# bancada_hx711_5.net
KiCad netlist of a schematic drawn in EAGLE
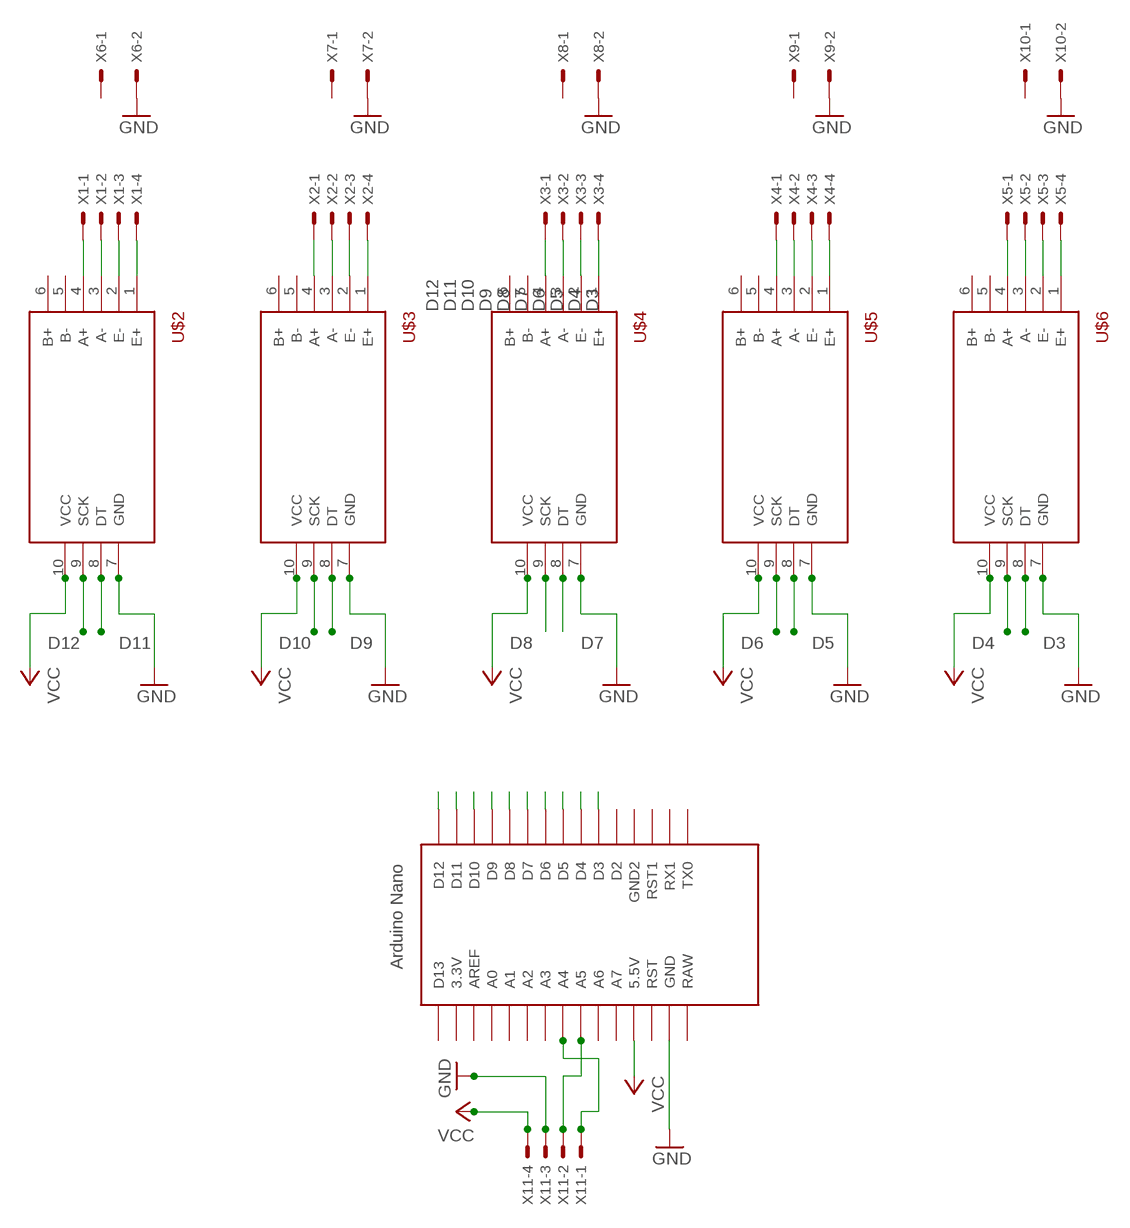
[diagram p0: schematic, sheet 1]

(export (version "E")
  (design (tool "Eeschema 10.0.6"))
  (components
    (comp (ref "U$1")
      (value "NANO")
      (footprint "eagle-import:NANO")
      (libsource (lib "eagle-import") (part "NANO"))
    )
    (comp (ref "U$2")
      (value "HX711-1")
      (footprint "eagle-import:HX711-1")
      (libsource (lib "eagle-import") (part "HX711-1"))
    )
    (comp (ref "U$3")
      (value "HX711-1")
      (footprint "eagle-import:HX711-1")
      (libsource (lib "eagle-import") (part "HX711-1"))
    )
    (comp (ref "U$4")
      (value "HX711-1")
      (footprint "eagle-import:HX711-1")
      (libsource (lib "eagle-import") (part "HX711-1"))
    )
    (comp (ref "U$5")
      (value "HX711-1")
      (footprint "eagle-import:HX711-1")
      (libsource (lib "eagle-import") (part "HX711-1"))
    )
    (comp (ref "U$6")
      (value "HX711-1")
      (footprint "eagle-import:HX711-1")
      (libsource (lib "eagle-import") (part "HX711-1"))
    )
    (comp (ref "X1")
      (value "KK-156-4")
      (footprint "eagle-import:KK-156-4")
      (fields (field (name "MF") "MOLEX"))
      (libsource (lib "eagle-import") (part "KK-156-4"))
    )
    (comp (ref "X2")
      (value "KK-156-4")
      (footprint "eagle-import:KK-156-4")
      (fields (field (name "MF") "MOLEX"))
      (libsource (lib "eagle-import") (part "KK-156-4"))
    )
    (comp (ref "X3")
      (value "KK-156-4")
      (footprint "eagle-import:KK-156-4")
      (fields (field (name "MF") "MOLEX"))
      (libsource (lib "eagle-import") (part "KK-156-4"))
    )
    (comp (ref "X4")
      (value "KK-156-4")
      (footprint "eagle-import:KK-156-4")
      (fields (field (name "MF") "MOLEX"))
      (libsource (lib "eagle-import") (part "KK-156-4"))
    )
    (comp (ref "X5")
      (value "KK-156-4")
      (footprint "eagle-import:KK-156-4")
      (fields (field (name "MF") "MOLEX"))
      (libsource (lib "eagle-import") (part "KK-156-4"))
    )
    (comp (ref "X6")
      (value "KK-156-2")
      (footprint "eagle-import:KK-156-2")
      (fields (field (name "MF") "MOLEX"))
      (libsource (lib "eagle-import") (part "KK-156-2"))
    )
    (comp (ref "X7")
      (value "KK-156-2")
      (footprint "eagle-import:KK-156-2")
      (fields (field (name "MF") "MOLEX"))
      (libsource (lib "eagle-import") (part "KK-156-2"))
    )
    (comp (ref "X8")
      (value "KK-156-2")
      (footprint "eagle-import:KK-156-2")
      (fields (field (name "MF") "MOLEX"))
      (libsource (lib "eagle-import") (part "KK-156-2"))
    )
    (comp (ref "X9")
      (value "KK-156-2")
      (footprint "eagle-import:KK-156-2")
      (fields (field (name "MF") "MOLEX"))
      (libsource (lib "eagle-import") (part "KK-156-2"))
    )
    (comp (ref "X10")
      (value "KK-156-2")
      (footprint "eagle-import:KK-156-2")
      (fields (field (name "MF") "MOLEX"))
      (libsource (lib "eagle-import") (part "KK-156-2"))
    )
    (comp (ref "X11")
      (value "KK-156-4")
      (footprint "eagle-import:KK-156-4")
      (fields (field (name "MF") "MOLEX"))
      (libsource (lib "eagle-import") (part "KK-156-4"))
    )
  )
  (nets
    (net (code "1") (name "/D3") (class "Default")
      (node (ref "U$1") (pin "D3") (pinfunction "D3_D3") (pintype "bidirectional"))
      (node (ref "U$6") (pin "8") (pinfunction "DT_8") (pintype "bidirectional"))
    )
    (net (code "2") (name "/D4") (class "Default")
      (node (ref "U$1") (pin "D4") (pinfunction "D4_D4") (pintype "bidirectional"))
      (node (ref "U$6") (pin "9") (pinfunction "SCK_9") (pintype "bidirectional"))
    )
    (net (code "3") (name "/D5") (class "Default")
      (node (ref "U$1") (pin "D5") (pinfunction "D5_D5") (pintype "bidirectional"))
      (node (ref "U$5") (pin "8") (pinfunction "DT_8") (pintype "bidirectional"))
    )
    (net (code "4") (name "/D6") (class "Default")
      (node (ref "U$1") (pin "D6") (pinfunction "D6_D6") (pintype "bidirectional"))
      (node (ref "U$5") (pin "9") (pinfunction "SCK_9") (pintype "bidirectional"))
    )
    (net (code "5") (name "/D7") (class "Default")
      (node (ref "U$1") (pin "D7") (pinfunction "D7_D7") (pintype "bidirectional"))
      (node (ref "U$4") (pin "8") (pinfunction "DT_8") (pintype "bidirectional"))
    )
    (net (code "6") (name "/D8") (class "Default")
      (node (ref "U$1") (pin "D8") (pinfunction "D8_D8") (pintype "bidirectional"))
      (node (ref "U$4") (pin "9") (pinfunction "SCK_9") (pintype "bidirectional"))
    )
    (net (code "7") (name "/D9") (class "Default")
      (node (ref "U$1") (pin "D9") (pinfunction "D9_D9") (pintype "bidirectional"))
      (node (ref "U$3") (pin "8") (pinfunction "DT_8") (pintype "bidirectional"))
    )
    (net (code "8") (name "/D10") (class "Default")
      (node (ref "U$1") (pin "D10") (pinfunction "D10_D10") (pintype "bidirectional"))
      (node (ref "U$3") (pin "9") (pinfunction "SCK_9") (pintype "bidirectional"))
    )
    (net (code "9") (name "/D11") (class "Default")
      (node (ref "U$1") (pin "D11") (pinfunction "D11_D11") (pintype "bidirectional"))
      (node (ref "U$2") (pin "8") (pinfunction "DT_8") (pintype "bidirectional"))
    )
    (net (code "10") (name "/D12") (class "Default")
      (node (ref "U$1") (pin "D12") (pinfunction "D12_D12") (pintype "bidirectional"))
      (node (ref "U$2") (pin "9") (pinfunction "SCK_9") (pintype "bidirectional"))
    )
    (net (code "11") (name "GND") (class "Default")
      (node (ref "U$1") (pin "GND") (pinfunction "GND_GND") (pintype "bidirectional"))
      (node (ref "U$2") (pin "7") (pinfunction "GND_7") (pintype "bidirectional"))
      (node (ref "U$3") (pin "7") (pinfunction "GND_7") (pintype "bidirectional"))
      (node (ref "U$4") (pin "7") (pinfunction "GND_7") (pintype "bidirectional"))
      (node (ref "U$5") (pin "7") (pinfunction "GND_7") (pintype "bidirectional"))
      (node (ref "U$6") (pin "7") (pinfunction "GND_7") (pintype "bidirectional"))
      (node (ref "X10") (pin "2") (pinfunction "S_2") (pintype "passive"))
      (node (ref "X11") (pin "3") (pinfunction "S_3") (pintype "passive"))
      (node (ref "X6") (pin "2") (pinfunction "S_2") (pintype "passive"))
      (node (ref "X7") (pin "2") (pinfunction "S_2") (pintype "passive"))
      (node (ref "X8") (pin "2") (pinfunction "S_2") (pintype "passive"))
      (node (ref "X9") (pin "2") (pinfunction "S_2") (pintype "passive"))
    )
    (net (code "12") (name "Net-(U$2-A+)") (class "Default")
      (node (ref "U$2") (pin "4") (pinfunction "A+_4") (pintype "bidirectional"))
      (node (ref "X1") (pin "1") (pinfunction "S_1") (pintype "passive"))
    )
    (net (code "13") (name "Net-(U$2-A-)") (class "Default")
      (node (ref "U$2") (pin "3") (pinfunction "A-_3") (pintype "bidirectional"))
      (node (ref "X1") (pin "2") (pinfunction "S_2") (pintype "passive"))
    )
    (net (code "14") (name "Net-(U$2-E+)") (class "Default")
      (node (ref "U$2") (pin "1") (pinfunction "E+_1") (pintype "bidirectional"))
      (node (ref "X1") (pin "4") (pinfunction "S_4") (pintype "passive"))
    )
    (net (code "15") (name "Net-(U$2-E-)") (class "Default")
      (node (ref "U$2") (pin "2") (pinfunction "E-_2") (pintype "bidirectional"))
      (node (ref "X1") (pin "3") (pinfunction "S_3") (pintype "passive"))
    )
    (net (code "16") (name "Net-(U$3-A+)") (class "Default")
      (node (ref "U$3") (pin "4") (pinfunction "A+_4") (pintype "bidirectional"))
      (node (ref "X2") (pin "1") (pinfunction "S_1") (pintype "passive"))
    )
    (net (code "17") (name "Net-(U$3-A-)") (class "Default")
      (node (ref "U$3") (pin "3") (pinfunction "A-_3") (pintype "bidirectional"))
      (node (ref "X2") (pin "2") (pinfunction "S_2") (pintype "passive"))
    )
    (net (code "18") (name "Net-(U$3-E+)") (class "Default")
      (node (ref "U$3") (pin "1") (pinfunction "E+_1") (pintype "bidirectional"))
      (node (ref "X2") (pin "4") (pinfunction "S_4") (pintype "passive"))
    )
    (net (code "19") (name "Net-(U$3-E-)") (class "Default")
      (node (ref "U$3") (pin "2") (pinfunction "E-_2") (pintype "bidirectional"))
      (node (ref "X2") (pin "3") (pinfunction "S_3") (pintype "passive"))
    )
    (net (code "20") (name "Net-(U$4-A+)") (class "Default")
      (node (ref "U$4") (pin "4") (pinfunction "A+_4") (pintype "bidirectional"))
      (node (ref "X3") (pin "1") (pinfunction "S_1") (pintype "passive"))
    )
    (net (code "21") (name "Net-(U$4-A-)") (class "Default")
      (node (ref "U$4") (pin "3") (pinfunction "A-_3") (pintype "bidirectional"))
      (node (ref "X3") (pin "2") (pinfunction "S_2") (pintype "passive"))
    )
    (net (code "22") (name "Net-(U$4-E+)") (class "Default")
      (node (ref "U$4") (pin "1") (pinfunction "E+_1") (pintype "bidirectional"))
      (node (ref "X3") (pin "4") (pinfunction "S_4") (pintype "passive"))
    )
    (net (code "23") (name "Net-(U$4-E-)") (class "Default")
      (node (ref "U$4") (pin "2") (pinfunction "E-_2") (pintype "bidirectional"))
      (node (ref "X3") (pin "3") (pinfunction "S_3") (pintype "passive"))
    )
    (net (code "24") (name "Net-(U$5-A+)") (class "Default")
      (node (ref "U$5") (pin "4") (pinfunction "A+_4") (pintype "bidirectional"))
      (node (ref "X4") (pin "1") (pinfunction "S_1") (pintype "passive"))
    )
    (net (code "25") (name "Net-(U$5-A-)") (class "Default")
      (node (ref "U$5") (pin "3") (pinfunction "A-_3") (pintype "bidirectional"))
      (node (ref "X4") (pin "2") (pinfunction "S_2") (pintype "passive"))
    )
    (net (code "26") (name "Net-(U$5-E+)") (class "Default")
      (node (ref "U$5") (pin "1") (pinfunction "E+_1") (pintype "bidirectional"))
      (node (ref "X4") (pin "4") (pinfunction "S_4") (pintype "passive"))
    )
    (net (code "27") (name "Net-(U$5-E-)") (class "Default")
      (node (ref "U$5") (pin "2") (pinfunction "E-_2") (pintype "bidirectional"))
      (node (ref "X4") (pin "3") (pinfunction "S_3") (pintype "passive"))
    )
    (net (code "28") (name "Net-(U$6-A+)") (class "Default")
      (node (ref "U$6") (pin "4") (pinfunction "A+_4") (pintype "bidirectional"))
      (node (ref "X5") (pin "1") (pinfunction "S_1") (pintype "passive"))
    )
    (net (code "29") (name "Net-(U$6-A-)") (class "Default")
      (node (ref "U$6") (pin "3") (pinfunction "A-_3") (pintype "bidirectional"))
      (node (ref "X5") (pin "2") (pinfunction "S_2") (pintype "passive"))
    )
    (net (code "30") (name "Net-(U$6-E+)") (class "Default")
      (node (ref "U$6") (pin "1") (pinfunction "E+_1") (pintype "bidirectional"))
      (node (ref "X5") (pin "4") (pinfunction "S_4") (pintype "passive"))
    )
    (net (code "31") (name "Net-(U$6-E-)") (class "Default")
      (node (ref "U$6") (pin "2") (pinfunction "E-_2") (pintype "bidirectional"))
      (node (ref "X5") (pin "3") (pinfunction "S_3") (pintype "passive"))
    )
    (net (code "32") (name "Net-(X11A-S)") (class "Default")
      (node (ref "U$1") (pin "A4") (pinfunction "A4_A4") (pintype "bidirectional"))
      (node (ref "X11") (pin "1") (pinfunction "S_1") (pintype "passive"))
    )
    (net (code "33") (name "Net-(X11B-S)") (class "Default")
      (node (ref "U$1") (pin "A5") (pinfunction "A5_A5") (pintype "bidirectional"))
      (node (ref "X11") (pin "2") (pinfunction "S_2") (pintype "passive"))
    )
    (net (code "34") (name "VCC") (class "Default")
      (node (ref "U$1") (pin "5V") (pinfunction "5.5V_5V") (pintype "bidirectional"))
      (node (ref "U$2") (pin "10") (pinfunction "VCC_10") (pintype "bidirectional"))
      (node (ref "U$3") (pin "10") (pinfunction "VCC_10") (pintype "bidirectional"))
      (node (ref "U$4") (pin "10") (pinfunction "VCC_10") (pintype "bidirectional"))
      (node (ref "U$5") (pin "10") (pinfunction "VCC_10") (pintype "bidirectional"))
      (node (ref "U$6") (pin "10") (pinfunction "VCC_10") (pintype "bidirectional"))
      (node (ref "X11") (pin "4") (pinfunction "S_4") (pintype "passive"))
    )
    (net (code "35") (name "unconnected-(U$1-GND2-PadGND1)") (class "Default")
      (node (ref "U$1") (pin "GND1") (pinfunction "GND2_GND1") (pintype "bidirectional"))
    )
    (net (code "36") (name "unconnected-(U$1-Pad3.3V)") (class "Default")
      (node (ref "U$1") (pin "3.3V") (pinfunction "3.3V_3.3V") (pintype "bidirectional"))
    )
    (net (code "37") (name "unconnected-(U$1-PadA0)") (class "Default")
      (node (ref "U$1") (pin "A0") (pinfunction "A0_A0") (pintype "bidirectional"))
    )
    (net (code "38") (name "unconnected-(U$1-PadA1)") (class "Default")
      (node (ref "U$1") (pin "A1") (pinfunction "A1_A1") (pintype "bidirectional"))
    )
    (net (code "39") (name "unconnected-(U$1-PadA2)") (class "Default")
      (node (ref "U$1") (pin "A2") (pinfunction "A2_A2") (pintype "bidirectional"))
    )
    (net (code "40") (name "unconnected-(U$1-PadA3)") (class "Default")
      (node (ref "U$1") (pin "A3") (pinfunction "A3_A3") (pintype "bidirectional"))
    )
    (net (code "41") (name "unconnected-(U$1-PadA6)") (class "Default")
      (node (ref "U$1") (pin "A6") (pinfunction "A6_A6") (pintype "bidirectional"))
    )
    (net (code "42") (name "unconnected-(U$1-PadA7)") (class "Default")
      (node (ref "U$1") (pin "A7") (pinfunction "A7_A7") (pintype "bidirectional"))
    )
    (net (code "43") (name "unconnected-(U$1-PadAREF)") (class "Default")
      (node (ref "U$1") (pin "AREF") (pinfunction "AREF_AREF") (pintype "bidirectional"))
    )
    (net (code "44") (name "unconnected-(U$1-PadD2)") (class "Default")
      (node (ref "U$1") (pin "D2") (pinfunction "D2_D2") (pintype "bidirectional"))
    )
    (net (code "45") (name "unconnected-(U$1-PadD13)") (class "Default")
      (node (ref "U$1") (pin "D13") (pinfunction "D13_D13") (pintype "bidirectional"))
    )
    (net (code "46") (name "unconnected-(U$1-PadICSP1)") (class "Default")
      (node (ref "U$1") (pin "ICSP1") (pinfunction "ICSP1_ICSP1") (pintype "bidirectional"))
    )
    (net (code "47") (name "unconnected-(U$1-PadICSP2)") (class "Default")
      (node (ref "U$1") (pin "ICSP2") (pinfunction "ICSP2_ICSP2") (pintype "bidirectional"))
    )
    (net (code "48") (name "unconnected-(U$1-PadICSP3)") (class "Default")
      (node (ref "U$1") (pin "ICSP3") (pinfunction "ICSP3_ICSP3") (pintype "bidirectional"))
    )
    (net (code "49") (name "unconnected-(U$1-PadICSP4)") (class "Default")
      (node (ref "U$1") (pin "ICSP4") (pinfunction "ICSP4_ICSP4") (pintype "bidirectional"))
    )
    (net (code "50") (name "unconnected-(U$1-PadICSP5)") (class "Default")
      (node (ref "U$1") (pin "ICSP5") (pinfunction "ICSP5_ICSP5") (pintype "bidirectional"))
    )
    (net (code "51") (name "unconnected-(U$1-PadICSP6)") (class "Default")
      (node (ref "U$1") (pin "ICSP6") (pinfunction "ICSP6_ICSP6") (pintype "bidirectional"))
    )
    (net (code "52") (name "unconnected-(U$1-PadRAW)") (class "Default")
      (node (ref "U$1") (pin "RAW") (pinfunction "RAW_RAW") (pintype "bidirectional"))
    )
    (net (code "53") (name "unconnected-(U$1-PadRST)") (class "Default")
      (node (ref "U$1") (pin "RST") (pinfunction "RST_RST") (pintype "bidirectional"))
    )
    (net (code "54") (name "unconnected-(U$1-PadRST1)") (class "Default")
      (node (ref "U$1") (pin "RST1") (pinfunction "RST1_RST1") (pintype "bidirectional"))
    )
    (net (code "55") (name "unconnected-(U$1-PadRX1)") (class "Default")
      (node (ref "U$1") (pin "RX1") (pinfunction "RX1_RX1") (pintype "bidirectional"))
    )
    (net (code "56") (name "unconnected-(U$1-PadTX0)") (class "Default")
      (node (ref "U$1") (pin "TX0") (pinfunction "TX0_TX0") (pintype "bidirectional"))
    )
    (net (code "57") (name "unconnected-(U$2-B+-Pad6)") (class "Default")
      (node (ref "U$2") (pin "6") (pinfunction "B+_6") (pintype "bidirectional"))
    )
    (net (code "58") (name "unconnected-(U$2-B--Pad5)") (class "Default")
      (node (ref "U$2") (pin "5") (pinfunction "B-_5") (pintype "bidirectional"))
    )
    (net (code "59") (name "unconnected-(U$3-B+-Pad6)") (class "Default")
      (node (ref "U$3") (pin "6") (pinfunction "B+_6") (pintype "bidirectional"))
    )
    (net (code "60") (name "unconnected-(U$3-B--Pad5)") (class "Default")
      (node (ref "U$3") (pin "5") (pinfunction "B-_5") (pintype "bidirectional"))
    )
    (net (code "61") (name "unconnected-(U$4-B+-Pad6)") (class "Default")
      (node (ref "U$4") (pin "6") (pinfunction "B+_6") (pintype "bidirectional"))
    )
    (net (code "62") (name "unconnected-(U$4-B--Pad5)") (class "Default")
      (node (ref "U$4") (pin "5") (pinfunction "B-_5") (pintype "bidirectional"))
    )
    (net (code "63") (name "unconnected-(U$5-B+-Pad6)") (class "Default")
      (node (ref "U$5") (pin "6") (pinfunction "B+_6") (pintype "bidirectional"))
    )
    (net (code "64") (name "unconnected-(U$5-B--Pad5)") (class "Default")
      (node (ref "U$5") (pin "5") (pinfunction "B-_5") (pintype "bidirectional"))
    )
    (net (code "65") (name "unconnected-(U$6-B+-Pad6)") (class "Default")
      (node (ref "U$6") (pin "6") (pinfunction "B+_6") (pintype "bidirectional"))
    )
    (net (code "66") (name "unconnected-(U$6-B--Pad5)") (class "Default")
      (node (ref "U$6") (pin "5") (pinfunction "B-_5") (pintype "bidirectional"))
    )
    (net (code "67") (name "unconnected-(X6A-S-Pad1)") (class "Default")
      (node (ref "X6") (pin "1") (pinfunction "S_1") (pintype "passive"))
    )
    (net (code "68") (name "unconnected-(X7A-S-Pad1)") (class "Default")
      (node (ref "X7") (pin "1") (pinfunction "S_1") (pintype "passive"))
    )
    (net (code "69") (name "unconnected-(X8A-S-Pad1)") (class "Default")
      (node (ref "X8") (pin "1") (pinfunction "S_1") (pintype "passive"))
    )
    (net (code "70") (name "unconnected-(X9A-S-Pad1)") (class "Default")
      (node (ref "X9") (pin "1") (pinfunction "S_1") (pintype "passive"))
    )
    (net (code "71") (name "unconnected-(X10A-S-Pad1)") (class "Default")
      (node (ref "X10") (pin "1") (pinfunction "S_1") (pintype "passive"))
    )
  )
)
